# DesignPrototype_RevC.net
KiCad netlist of a schematic drawn in EAGLE
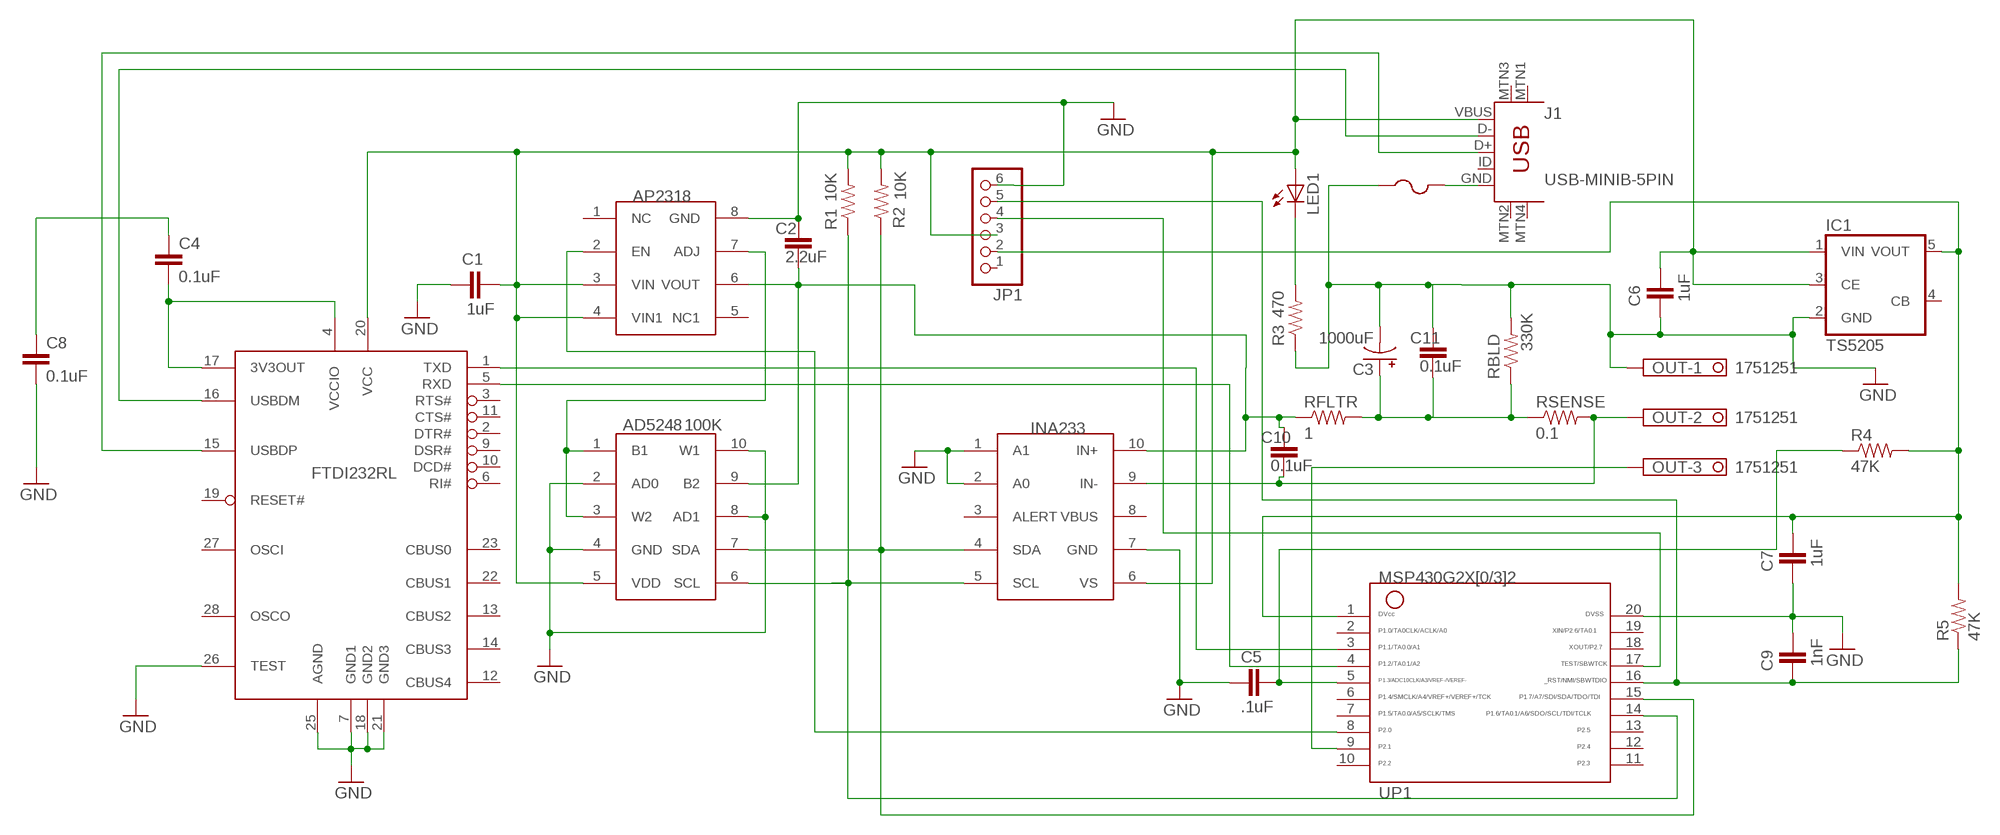
[diagram p0: schematic, sheet 1]

(export (version "E")
  (design (tool "Eeschema 10.0.6"))
  (components
    (comp (ref "AD5248")
      (value "100K")
      (footprint "eagle-import:MSOP-10")
      (libsource (lib "eagle-import") (part "AD5248"))
    )
    (comp (ref "AP2318")
      (value "AP2318")
      (footprint "eagle-import:SOIC-8")
      (libsource (lib "eagle-import") (part "AP2318"))
    )
    (comp (ref "C1")
      (value "1uF")
      (footprint "eagle-import:1206")
      (libsource (lib "eagle-import") (part "CAP1206"))
    )
    (comp (ref "C2")
      (value "2.2uF")
      (footprint "eagle-import:1206")
      (libsource (lib "eagle-import") (part "CAP1206"))
    )
    (comp (ref "C3")
      (value "1000uF")
      (footprint "eagle-import:PANASONIC_F")
      (libsource (lib "eagle-import") (part "CPOL-USF"))
    )
    (comp (ref "C4")
      (value "0.1uF")
      (footprint "eagle-import:1206")
      (libsource (lib "eagle-import") (part "CAP1206"))
    )
    (comp (ref "C5")
      (value ".1uF")
      (footprint "eagle-import:1206")
      (libsource (lib "eagle-import") (part "CAP1206"))
    )
    (comp (ref "C6")
      (value "1uF")
      (footprint "eagle-import:1206")
      (libsource (lib "eagle-import") (part "CAP1206"))
    )
    (comp (ref "C7")
      (value "1uF")
      (footprint "eagle-import:1206")
      (libsource (lib "eagle-import") (part "CAP1206"))
    )
    (comp (ref "C8")
      (value "0.1uF")
      (footprint "eagle-import:1206")
      (libsource (lib "eagle-import") (part "CAP1206"))
    )
    (comp (ref "C9")
      (value "1nF")
      (footprint "eagle-import:1206")
      (libsource (lib "eagle-import") (part "CAP1206"))
    )
    (comp (ref "C10")
      (value "0.1uF")
      (footprint "eagle-import:1206")
      (libsource (lib "eagle-import") (part "CAP1206"))
    )
    (comp (ref "C11")
      (value "0.1uF")
      (footprint "eagle-import:1206")
      (libsource (lib "eagle-import") (part "CAP1206"))
    )
    (comp (ref "FTDI232RL")
      (value "FT232RL")
      (footprint "eagle-import:SSOP28DB")
      (libsource (lib "eagle-import") (part "FT232RL"))
    )
    (comp (ref "FUSE1")
      (value "PTCFUSE-1206")
      (footprint "eagle-import:R1206")
      (libsource (lib "eagle-import") (part "PTCFUSE-1206"))
    )
    (comp (ref "IC1")
      (value "TS5205")
      (footprint "eagle-import:SOT25")
      (libsource (lib "eagle-import") (part "TS5205"))
    )
    (comp (ref "INA233")
      (value "INA233")
      (footprint "eagle-import:VSSOP-10")
      (libsource (lib "eagle-import") (part "INA233"))
    )
    (comp (ref "J1")
      (value "USB-MINIB-5PIN")
      (footprint "eagle-import:USB-MINIB")
      (libsource (lib "eagle-import") (part "USB-MINIB-5PIN"))
    )
    (comp (ref "JP1")
      (value "PINHD-1X6")
      (footprint "eagle-import:1X06")
      (libsource (lib "eagle-import") (part "PINHD-1X6"))
    )
    (comp (ref "LED1")
      (value "LEDCHIPLED_1206")
      (footprint "eagle-import:CHIPLED_1206")
      (libsource (lib "eagle-import") (part "LEDCHIPLED_1206"))
    )
    (comp (ref "OUT")
      (value "1751251")
      (footprint "eagle-import:1751251")
      (libsource (lib "eagle-import") (part "1751251"))
    )
    (comp (ref "R1")
      (value "10K")
      (footprint "eagle-import:1206")
      (libsource (lib "eagle-import") (part "RESISTOR1206"))
    )
    (comp (ref "R2")
      (value "10K")
      (footprint "eagle-import:1206")
      (libsource (lib "eagle-import") (part "RESISTOR1206"))
    )
    (comp (ref "R3")
      (value "470")
      (footprint "eagle-import:1206")
      (libsource (lib "eagle-import") (part "RESISTOR1206"))
    )
    (comp (ref "R4")
      (value "47K")
      (footprint "eagle-import:1206")
      (libsource (lib "eagle-import") (part "RESISTOR1206"))
    )
    (comp (ref "R5")
      (value "47K")
      (footprint "eagle-import:1206")
      (libsource (lib "eagle-import") (part "RESISTOR1206"))
    )
    (comp (ref "RBLD")
      (value "330K")
      (footprint "eagle-import:1206")
      (libsource (lib "eagle-import") (part "RESISTOR1206"))
    )
    (comp (ref "RFLTR")
      (value "1")
      (footprint "eagle-import:1206")
      (libsource (lib "eagle-import") (part "SparkFun-Resistors_RESISTOR1206"))
    )
    (comp (ref "RSENSE")
      (value "0.1")
      (footprint "eagle-import:1206")
      (libsource (lib "eagle-import") (part "SparkFun-Resistors_RESISTOR1206"))
    )
    (comp (ref "UP1")
      (value "MSP430")
      (footprint "eagle-import:PW20")
      (libsource (lib "eagle-import") (part "G2X[0/3]2---PW20"))
    )
  )
  (nets
    (net (code "1") (name "GND") (class "Default")
      (node (ref "AD5248") (pin "10") (pinfunction "W1_10") (pintype "bidirectional"))
      (node (ref "AD5248") (pin "2") (pinfunction "AD0_2") (pintype "bidirectional"))
      (node (ref "AD5248") (pin "4") (pinfunction "GND_4") (pintype "bidirectional"))
      (node (ref "AD5248") (pin "8") (pinfunction "AD1_8") (pintype "bidirectional"))
      (node (ref "AP2318") (pin "8") (pinfunction "GND_8") (pintype "bidirectional"))
      (node (ref "C1") (pin "1") (pinfunction "1_1") (pintype "passive"))
      (node (ref "C11") (pin "1") (pinfunction "1_1") (pintype "passive"))
      (node (ref "C2") (pin "1") (pinfunction "1_1") (pintype "passive"))
      (node (ref "C3") (pin "-") (pinfunction "-_-") (pintype "passive"))
      (node (ref "C5") (pin "1") (pinfunction "1_1") (pintype "passive"))
      (node (ref "C6") (pin "1") (pinfunction "1_1") (pintype "passive"))
      (node (ref "C7") (pin "1") (pinfunction "1_1") (pintype "passive"))
      (node (ref "C8") (pin "2") (pinfunction "2_2") (pintype "passive"))
      (node (ref "C9") (pin "2") (pinfunction "2_2") (pintype "passive"))
      (node (ref "FTDI232RL") (pin "18") (pinfunction "GND2_18") (pintype "power_in"))
      (node (ref "FTDI232RL") (pin "21") (pinfunction "GND3_21") (pintype "power_in"))
      (node (ref "FTDI232RL") (pin "25") (pinfunction "AGND_25") (pintype "power_in"))
      (node (ref "FTDI232RL") (pin "26") (pinfunction "TEST_26") (pintype "input"))
      (node (ref "FTDI232RL") (pin "7") (pinfunction "GND1_7") (pintype "power_in"))
      (node (ref "FUSE1") (pin "1") (pinfunction "1_1") (pintype "passive"))
      (node (ref "IC1") (pin "2") (pinfunction "GND_2") (pintype "passive"))
      (node (ref "INA233") (pin "1") (pinfunction "A1_1") (pintype "bidirectional"))
      (node (ref "INA233") (pin "2") (pinfunction "A0_2") (pintype "bidirectional"))
      (node (ref "INA233") (pin "7") (pinfunction "GND_7") (pintype "bidirectional"))
      (node (ref "JP1") (pin "6") (pinfunction "6_6") (pintype "passive"))
      (node (ref "OUT") (pin "1") (pinfunction "K_1") (pintype "passive"))
      (node (ref "R3") (pin "1") (pinfunction "1_1") (pintype "passive"))
      (node (ref "RBLD") (pin "2") (pinfunction "2_2") (pintype "passive"))
      (node (ref "UP1") (pin "20") (pinfunction "20_20") (pintype "bidirectional"))
    )
    (net (code "2") (name "Net-(AD5248-B1)") (class "Default")
      (node (ref "AD5248") (pin "1") (pinfunction "B1_1") (pintype "bidirectional"))
      (node (ref "AD5248") (pin "3") (pinfunction "W2_3") (pintype "bidirectional"))
      (node (ref "AP2318") (pin "7") (pinfunction "ADJ_7") (pintype "bidirectional"))
    )
    (net (code "3") (name "Net-(AD5248-B2)") (class "Default")
      (node (ref "AD5248") (pin "9") (pinfunction "B2_9") (pintype "bidirectional"))
      (node (ref "AP2318") (pin "6") (pinfunction "VOUT_6") (pintype "bidirectional"))
      (node (ref "C10") (pin "1") (pinfunction "1_1") (pintype "passive"))
      (node (ref "C2") (pin "2") (pinfunction "2_2") (pintype "passive"))
      (node (ref "INA233") (pin "10") (pinfunction "IN+_10") (pintype "input"))
      (node (ref "RFLTR") (pin "1") (pinfunction "1_1") (pintype "passive"))
    )
    (net (code "4") (name "Net-(AD5248-SCL)") (class "Default")
      (node (ref "AD5248") (pin "6") (pinfunction "SCL_6") (pintype "input"))
      (node (ref "INA233") (pin "5") (pinfunction "SCL_5") (pintype "input"))
      (node (ref "R1") (pin "1") (pinfunction "1_1") (pintype "passive"))
      (node (ref "UP1") (pin "14") (pinfunction "14_14") (pintype "bidirectional"))
    )
    (net (code "5") (name "Net-(AD5248-SDA)") (class "Default")
      (node (ref "AD5248") (pin "7") (pinfunction "SDA_7") (pintype "input"))
      (node (ref "INA233") (pin "4") (pinfunction "SDA_4") (pintype "input"))
      (node (ref "R2") (pin "1") (pinfunction "1_1") (pintype "passive"))
      (node (ref "UP1") (pin "15") (pinfunction "15_15") (pintype "bidirectional"))
    )
    (net (code "6") (name "Net-(AD5248-VDD)") (class "Default")
      (node (ref "AD5248") (pin "5") (pinfunction "VDD_5") (pintype "power_in"))
      (node (ref "AP2318") (pin "3") (pinfunction "VIN_3") (pintype "power_in"))
      (node (ref "AP2318") (pin "4") (pinfunction "VIN1_4") (pintype "power_in"))
      (node (ref "C1") (pin "2") (pinfunction "2_2") (pintype "passive"))
      (node (ref "C6") (pin "2") (pinfunction "2_2") (pintype "passive"))
      (node (ref "FTDI232RL") (pin "20") (pinfunction "VCC_20") (pintype "power_in"))
      (node (ref "IC1") (pin "1") (pinfunction "VIN_1") (pintype "input"))
      (node (ref "IC1") (pin "3") (pinfunction "CE_3") (pintype "input"))
      (node (ref "INA233") (pin "6") (pinfunction "VS_6") (pintype "power_in"))
      (node (ref "J1") (pin "VBUS") (pinfunction "VBUS_VBUS") (pintype "bidirectional"))
      (node (ref "JP1") (pin "3") (pinfunction "3_3") (pintype "passive"))
      (node (ref "LED1") (pin "A") (pinfunction "A_A") (pintype "passive"))
      (node (ref "R1") (pin "2") (pinfunction "2_2") (pintype "passive"))
      (node (ref "R2") (pin "2") (pinfunction "2_2") (pintype "passive"))
    )
    (net (code "7") (name "Net-(AP2318-EN)") (class "Default")
      (node (ref "AP2318") (pin "2") (pinfunction "EN_2") (pintype "bidirectional"))
      (node (ref "UP1") (pin "8") (pinfunction "8_8") (pintype "bidirectional"))
    )
    (net (code "8") (name "Net-(C4-Pad1)") (class "Default")
      (node (ref "C4") (pin "1") (pinfunction "1_1") (pintype "passive"))
      (node (ref "C8") (pin "1") (pinfunction "1_1") (pintype "passive"))
    )
    (net (code "9") (name "Net-(C5-Pad2)") (class "Default")
      (node (ref "C5") (pin "2") (pinfunction "2_2") (pintype "passive"))
      (node (ref "R4") (pin "1") (pinfunction "1_1") (pintype "passive"))
      (node (ref "UP1") (pin "5") (pinfunction "5_5") (pintype "bidirectional"))
    )
    (net (code "10") (name "Net-(C9-Pad1)") (class "Default")
      (node (ref "C9") (pin "1") (pinfunction "1_1") (pintype "passive"))
      (node (ref "JP1") (pin "5") (pinfunction "5_5") (pintype "passive"))
      (node (ref "R5") (pin "1") (pinfunction "1_1") (pintype "passive"))
      (node (ref "UP1") (pin "16") (pinfunction "16_16") (pintype "bidirectional"))
    )
    (net (code "11") (name "Net-(C11-Pad2)") (class "Default")
      (node (ref "C11") (pin "2") (pinfunction "2_2") (pintype "passive"))
      (node (ref "C3") (pin "+") (pinfunction "+_+") (pintype "passive"))
      (node (ref "RBLD") (pin "1") (pinfunction "1_1") (pintype "passive"))
      (node (ref "RFLTR") (pin "2") (pinfunction "2_2") (pintype "passive"))
      (node (ref "RSENSE") (pin "1") (pinfunction "1_1") (pintype "passive"))
    )
    (net (code "12") (name "Net-(FTDI232RL-3V3OUT)") (class "Default")
      (node (ref "C4") (pin "2") (pinfunction "2_2") (pintype "passive"))
      (node (ref "FTDI232RL") (pin "17") (pinfunction "3V3OUT_17") (pintype "output"))
      (node (ref "FTDI232RL") (pin "4") (pinfunction "VCCIO_4") (pintype "power_in"))
    )
    (net (code "13") (name "Net-(FTDI232RL-RXD)") (class "Default")
      (node (ref "FTDI232RL") (pin "5") (pinfunction "RXD_5") (pintype "input"))
      (node (ref "UP1") (pin "4") (pinfunction "4_4") (pintype "bidirectional"))
    )
    (net (code "14") (name "Net-(FTDI232RL-TXD)") (class "Default")
      (node (ref "FTDI232RL") (pin "1") (pinfunction "TXD_1") (pintype "output"))
      (node (ref "UP1") (pin "3") (pinfunction "3_3") (pintype "bidirectional"))
    )
    (net (code "15") (name "Net-(FTDI232RL-USBDM)") (class "Default")
      (node (ref "FTDI232RL") (pin "16") (pinfunction "USBDM_16") (pintype "bidirectional"))
      (node (ref "J1") (pin "D-") (pinfunction "D-_D-") (pintype "bidirectional"))
    )
    (net (code "16") (name "Net-(FTDI232RL-USBDP)") (class "Default")
      (node (ref "FTDI232RL") (pin "15") (pinfunction "USBDP_15") (pintype "bidirectional"))
      (node (ref "J1") (pin "D+") (pinfunction "D+_D+") (pintype "bidirectional"))
    )
    (net (code "17") (name "Net-(FUSE1-Pad2)") (class "Default")
      (node (ref "FUSE1") (pin "2") (pinfunction "2_2") (pintype "passive"))
      (node (ref "J1") (pin "GND") (pinfunction "GND_GND") (pintype "bidirectional"))
    )
    (net (code "18") (name "Net-(IC1-VOUT)") (class "Default")
      (node (ref "C7") (pin "2") (pinfunction "2_2") (pintype "passive"))
      (node (ref "IC1") (pin "5") (pinfunction "VOUT_5") (pintype "passive"))
      (node (ref "JP1") (pin "2") (pinfunction "2_2") (pintype "passive"))
      (node (ref "R4") (pin "2") (pinfunction "2_2") (pintype "passive"))
      (node (ref "R5") (pin "2") (pinfunction "2_2") (pintype "passive"))
      (node (ref "UP1") (pin "1") (pinfunction "1_1") (pintype "bidirectional"))
    )
    (net (code "19") (name "Net-(INA233-IN-)") (class "Default")
      (node (ref "C10") (pin "2") (pinfunction "2_2") (pintype "passive"))
      (node (ref "INA233") (pin "9") (pinfunction "IN-_9") (pintype "input"))
      (node (ref "OUT") (pin "2") (pinfunction "K_2") (pintype "passive"))
      (node (ref "RSENSE") (pin "2") (pinfunction "2_2") (pintype "passive"))
    )
    (net (code "20") (name "Net-(JP1-Pad4)") (class "Default")
      (node (ref "JP1") (pin "4") (pinfunction "4_4") (pintype "passive"))
      (node (ref "UP1") (pin "17") (pinfunction "17_17") (pintype "bidirectional"))
    )
    (net (code "21") (name "Net-(LED1-PadC)") (class "Default")
      (node (ref "LED1") (pin "C") (pinfunction "C_C") (pintype "passive"))
      (node (ref "R3") (pin "2") (pinfunction "2_2") (pintype "passive"))
    )
    (net (code "22") (name "Net-(OUTC-K)") (class "Default")
      (node (ref "OUT") (pin "3") (pinfunction "K_3") (pintype "passive"))
      (node (ref "UP1") (pin "9") (pinfunction "9_9") (pintype "bidirectional"))
    )
    (net (code "23") (name "unconnected-(AP2318-NC-Pad1)") (class "Default")
      (node (ref "AP2318") (pin "1") (pinfunction "NC_1") (pintype "no_connect"))
    )
    (net (code "24") (name "unconnected-(AP2318-NC1-Pad5)") (class "Default")
      (node (ref "AP2318") (pin "5") (pinfunction "NC1_5") (pintype "no_connect"))
    )
    (net (code "25") (name "unconnected-(FTDI232RL-CBUS0-Pad23)") (class "Default")
      (node (ref "FTDI232RL") (pin "23") (pinfunction "CBUS0_23") (pintype "bidirectional"))
    )
    (net (code "26") (name "unconnected-(FTDI232RL-CBUS1-Pad22)") (class "Default")
      (node (ref "FTDI232RL") (pin "22") (pinfunction "CBUS1_22") (pintype "bidirectional"))
    )
    (net (code "27") (name "unconnected-(FTDI232RL-CBUS2-Pad13)") (class "Default")
      (node (ref "FTDI232RL") (pin "13") (pinfunction "CBUS2_13") (pintype "bidirectional"))
    )
    (net (code "28") (name "unconnected-(FTDI232RL-CBUS3-Pad14)") (class "Default")
      (node (ref "FTDI232RL") (pin "14") (pinfunction "CBUS3_14") (pintype "bidirectional"))
    )
    (net (code "29") (name "unconnected-(FTDI232RL-CBUS4-Pad12)") (class "Default")
      (node (ref "FTDI232RL") (pin "12") (pinfunction "CBUS4_12") (pintype "bidirectional"))
    )
    (net (code "30") (name "unconnected-(FTDI232RL-CTS#-Pad11)") (class "Default")
      (node (ref "FTDI232RL") (pin "11") (pinfunction "CTS#_11") (pintype "input"))
    )
    (net (code "31") (name "unconnected-(FTDI232RL-DCD#-Pad10)") (class "Default")
      (node (ref "FTDI232RL") (pin "10") (pinfunction "DCD#_10") (pintype "input"))
    )
    (net (code "32") (name "unconnected-(FTDI232RL-DSR#-Pad9)") (class "Default")
      (node (ref "FTDI232RL") (pin "9") (pinfunction "DSR#_9") (pintype "input"))
    )
    (net (code "33") (name "unconnected-(FTDI232RL-DTR#-Pad2)") (class "Default")
      (node (ref "FTDI232RL") (pin "2") (pinfunction "DTR#_2") (pintype "output"))
    )
    (net (code "34") (name "unconnected-(FTDI232RL-OSCI-Pad27)") (class "Default")
      (node (ref "FTDI232RL") (pin "27") (pinfunction "OSCI_27") (pintype "input"))
    )
    (net (code "35") (name "unconnected-(FTDI232RL-OSCO-Pad28)") (class "Default")
      (node (ref "FTDI232RL") (pin "28") (pinfunction "OSCO_28") (pintype "output"))
    )
    (net (code "36") (name "unconnected-(FTDI232RL-RESET#-Pad19)") (class "Default")
      (node (ref "FTDI232RL") (pin "19") (pinfunction "RESET#_19") (pintype "input"))
    )
    (net (code "37") (name "unconnected-(FTDI232RL-RI#-Pad6)") (class "Default")
      (node (ref "FTDI232RL") (pin "6") (pinfunction "RI#_6") (pintype "input"))
    )
    (net (code "38") (name "unconnected-(FTDI232RL-RTS#-Pad3)") (class "Default")
      (node (ref "FTDI232RL") (pin "3") (pinfunction "RTS#_3") (pintype "output"))
    )
    (net (code "39") (name "unconnected-(IC1-CB-Pad4)") (class "Default")
      (node (ref "IC1") (pin "4") (pinfunction "CB_4") (pintype "input"))
    )
    (net (code "40") (name "unconnected-(INA233-ALERT-Pad3)") (class "Default")
      (node (ref "INA233") (pin "3") (pinfunction "ALERT_3") (pintype "input"))
    )
    (net (code "41") (name "unconnected-(INA233-VBUS-Pad8)") (class "Default")
      (node (ref "INA233") (pin "8") (pinfunction "VBUS_8") (pintype "bidirectional"))
    )
    (net (code "42") (name "unconnected-(J1-MTN1-PadMTN3)") (class "Default")
      (node (ref "J1") (pin "MTN3") (pinfunction "MTN1_MTN3") (pintype "bidirectional"))
    )
    (net (code "43") (name "unconnected-(J1-MTN2-PadMTN1)") (class "Default")
      (node (ref "J1") (pin "MTN1") (pinfunction "MTN2_MTN1") (pintype "bidirectional"))
    )
    (net (code "44") (name "unconnected-(J1-MTN3-PadMTN2)") (class "Default")
      (node (ref "J1") (pin "MTN2") (pinfunction "MTN3_MTN2") (pintype "bidirectional"))
    )
    (net (code "45") (name "unconnected-(J1-PadID)") (class "Default")
      (node (ref "J1") (pin "ID") (pinfunction "ID_ID") (pintype "bidirectional"))
    )
    (net (code "46") (name "unconnected-(J1-PadMTN4)") (class "Default")
      (node (ref "J1") (pin "MTN4") (pinfunction "MTN4_MTN4") (pintype "bidirectional"))
    )
    (net (code "47") (name "unconnected-(JP1-Pad1)") (class "Default")
      (node (ref "JP1") (pin "1") (pinfunction "1_1") (pintype "passive"))
    )
    (net (code "48") (name "unconnected-(UP1-Pad2)") (class "Default")
      (node (ref "UP1") (pin "2") (pinfunction "2_2") (pintype "bidirectional"))
    )
    (net (code "49") (name "unconnected-(UP1-Pad6)") (class "Default")
      (node (ref "UP1") (pin "6") (pinfunction "6_6") (pintype "bidirectional"))
    )
    (net (code "50") (name "unconnected-(UP1-Pad7)") (class "Default")
      (node (ref "UP1") (pin "7") (pinfunction "7_7") (pintype "bidirectional"))
    )
    (net (code "51") (name "unconnected-(UP1-Pad10)") (class "Default")
      (node (ref "UP1") (pin "10") (pinfunction "10_10") (pintype "bidirectional"))
    )
    (net (code "52") (name "unconnected-(UP1-Pad11)") (class "Default")
      (node (ref "UP1") (pin "11") (pinfunction "11_11") (pintype "bidirectional"))
    )
    (net (code "53") (name "unconnected-(UP1-Pad12)") (class "Default")
      (node (ref "UP1") (pin "12") (pinfunction "12_12") (pintype "bidirectional"))
    )
    (net (code "54") (name "unconnected-(UP1-Pad13)") (class "Default")
      (node (ref "UP1") (pin "13") (pinfunction "13_13") (pintype "bidirectional"))
    )
    (net (code "55") (name "unconnected-(UP1-Pad18)") (class "Default")
      (node (ref "UP1") (pin "18") (pinfunction "18_18") (pintype "bidirectional"))
    )
    (net (code "56") (name "unconnected-(UP1-Pad19)") (class "Default")
      (node (ref "UP1") (pin "19") (pinfunction "19_19") (pintype "bidirectional"))
    )
  )
)
